# Short-round_to_Regular_Header.net
KiCad netlist of a schematic drawn in EAGLE
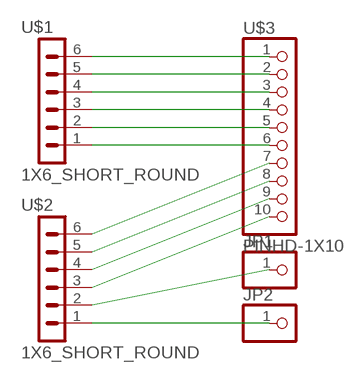
[diagram p0: schematic, sheet 1]

(export (version "E")
  (design (tool "Eeschema 10.0.6"))
  (components
    (comp (ref "JP1")
      (value "PINHD-1X1")
      (footprint "eagle-import:1X01")
      (libsource (lib "eagle-import") (part "PINHD-1X1"))
    )
    (comp (ref "JP2")
      (value "PINHD-1X1")
      (footprint "eagle-import:1X01")
      (libsource (lib "eagle-import") (part "PINHD-1X1"))
    )
    (comp (ref "U$1")
      (value "1X6_SHORT_ROUND")
      (footprint "eagle-import:1X6_SHORT_ROUND")
      (libsource (lib "eagle-import") (part "1X6_SHORT_ROUND"))
    )
    (comp (ref "U$2")
      (value "1X6_SHORT_ROUND")
      (footprint "eagle-import:1X6_SHORT_ROUND")
      (libsource (lib "eagle-import") (part "1X6_SHORT_ROUND"))
    )
    (comp (ref "U$3")
      (value "PINHD-1X10")
      (footprint "eagle-import:1X10-BIG")
      (libsource (lib "eagle-import") (part "PINHD-1X10"))
    )
  )
  (nets
    (net (code "1") (name "Net-(JP1-Pad1)") (class "Default")
      (node (ref "JP1") (pin "1") (pinfunction "1_1") (pintype "passive"))
      (node (ref "U$2") (pin "2") (pinfunction "2_2") (pintype "passive"))
    )
    (net (code "2") (name "Net-(JP2-Pad1)") (class "Default")
      (node (ref "JP2") (pin "1") (pinfunction "1_1") (pintype "passive"))
      (node (ref "U$2") (pin "1") (pinfunction "1_1") (pintype "passive"))
    )
    (net (code "3") (name "Net-(U$1-Pad1)") (class "Default")
      (node (ref "U$1") (pin "1") (pinfunction "1_1") (pintype "passive"))
      (node (ref "U$3") (pin "6") (pinfunction "6_6") (pintype "passive"))
    )
    (net (code "4") (name "Net-(U$1-Pad2)") (class "Default")
      (node (ref "U$1") (pin "2") (pinfunction "2_2") (pintype "passive"))
      (node (ref "U$3") (pin "5") (pinfunction "5_5") (pintype "passive"))
    )
    (net (code "5") (name "Net-(U$1-Pad3)") (class "Default")
      (node (ref "U$1") (pin "3") (pinfunction "3_3") (pintype "passive"))
      (node (ref "U$3") (pin "4") (pinfunction "4_4") (pintype "passive"))
    )
    (net (code "6") (name "Net-(U$1-Pad4)") (class "Default")
      (node (ref "U$1") (pin "4") (pinfunction "4_4") (pintype "passive"))
      (node (ref "U$3") (pin "3") (pinfunction "3_3") (pintype "passive"))
    )
    (net (code "7") (name "Net-(U$1-Pad5)") (class "Default")
      (node (ref "U$1") (pin "5") (pinfunction "5_5") (pintype "passive"))
      (node (ref "U$3") (pin "2") (pinfunction "2_2") (pintype "passive"))
    )
    (net (code "8") (name "Net-(U$1-Pad6)") (class "Default")
      (node (ref "U$1") (pin "6") (pinfunction "6_6") (pintype "passive"))
      (node (ref "U$3") (pin "1") (pinfunction "1_1") (pintype "passive"))
    )
    (net (code "9") (name "Net-(U$2-Pad3)") (class "Default")
      (node (ref "U$2") (pin "3") (pinfunction "3_3") (pintype "passive"))
      (node (ref "U$3") (pin "10") (pinfunction "10_10") (pintype "passive"))
    )
    (net (code "10") (name "Net-(U$2-Pad4)") (class "Default")
      (node (ref "U$2") (pin "4") (pinfunction "4_4") (pintype "passive"))
      (node (ref "U$3") (pin "9") (pinfunction "9_9") (pintype "passive"))
    )
    (net (code "11") (name "Net-(U$2-Pad5)") (class "Default")
      (node (ref "U$2") (pin "5") (pinfunction "5_5") (pintype "passive"))
      (node (ref "U$3") (pin "8") (pinfunction "8_8") (pintype "passive"))
    )
    (net (code "12") (name "Net-(U$2-Pad6)") (class "Default")
      (node (ref "U$2") (pin "6") (pinfunction "6_6") (pintype "passive"))
      (node (ref "U$3") (pin "7") (pinfunction "7_7") (pintype "passive"))
    )
  )
)
